# Sheet1.net
KiCad netlist of a schematic drawn in Altium Designer
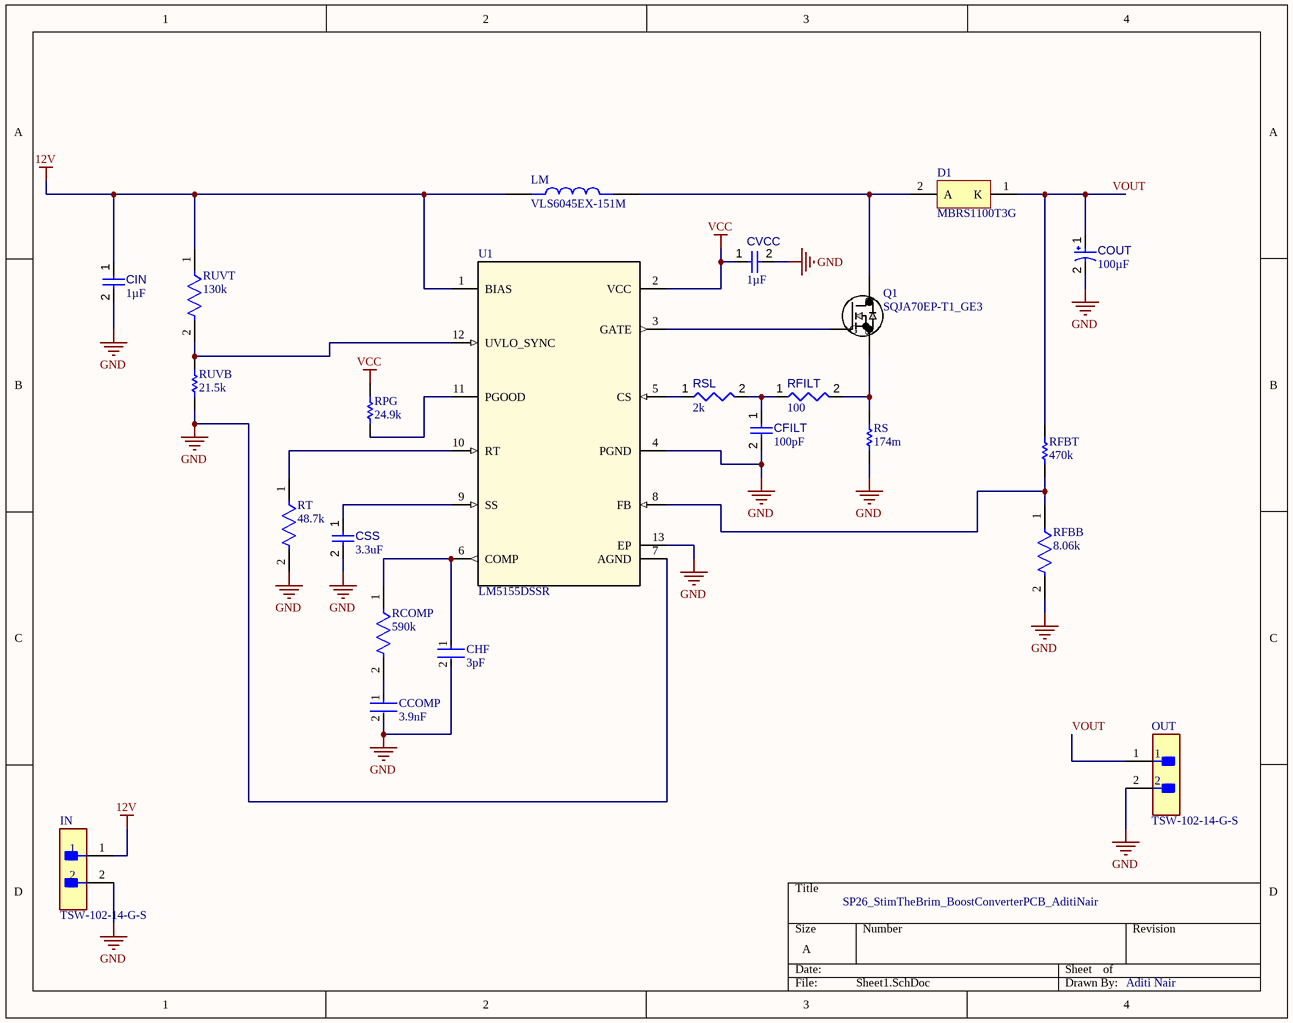
[diagram p0: Sheet1.SchDoc]

(export (version "E")
  (design (tool "Eeschema 10.0.6"))
  (components
    (comp (ref "CCOMP")
      (value "3.9nF")
      (footprint "FP-C1206C-EB-MFG")
      (description "C1206 3,900 pF C0G 5.00% 250 V")
      (fields
        (field (name "MANUFACTURER PART NUMBER") "C1206C392JAGACTU")
        (field (name "OCTOPART") "https://octopart.com/c1206c392jagactu-kemet-88376556")
      )
      (libsource (lib "Altium Content Vault") (part "b4654b650e69147ec39a6b967a45e02"))
    )
    (comp (ref "CFILT")
      (value "100pF")
      (footprint "CAPC0603(1608)100_L")
      (description "Chip Capacitor, 4.7µF +/-20%, 10V, 0603, Thickness 1 mm")
      (fields (field (name "TOLERANCE") "10%"))
      (libsource (lib "Aditi Nair") (part "CAP-NP-2"))
    )
    (comp (ref "CHF")
      (value "3pF")
      (footprint "FP-C0603C-CF-MFG")
      (description "CAP CER 3PF 50V NP0 0603")
      (fields
        (field (name "MANUFACTURER PART NUMBER") "C0603C309D5GAC7867")
        (field (name "MANUFACTURER") "KEMET")
      )
      (libsource (lib "Altium Content Vault") (part "b4654b650e69147ec39a6b967a45e02"))
    )
    (comp (ref "CIN")
      (value "1µF")
      (footprint "CAPC1608X90X35ML15T15")
      (description "Chip Capacitor, 1 uF, +/- 10%, 16 V, 0603 (1608 Metric)")
      (fields (field (name "TOLERANCE") "10%") (field (name "Comment") "Capacitor 1uF +/- 10% 16V 0603"))
      (libsource (lib "Aditi Nair") (part "CAP-NP-2"))
    )
    (comp (ref "COUT")
      (value "100µF")
      (footprint "CAPPR65-500-1600X1000X1700")
      (description "Aluminum Electrolytic Capacitor, 100 uF, +/- 20%, 100 V, -40 to 85 degC, 2-Pin THD, RoHS, Bulk")
      (fields (field (name "MANUFACTURER") "Panasonic") (field (name "TOLERANCE") "20%"))
      (libsource (lib "Aditi Nair") (part "CAP-P-2"))
    )
    (comp (ref "CSS")
      (value "3.3uF")
      (footprint "CAPC1608X90X35ML15T15")
      (description "Chip Capacitor, 1 uF, +/- 10%, 16 V, 0603 (1608 Metric)")
      (fields (field (name "TOLERANCE") "10%") (field (name "Comment") "Capacitor 1uF +/- 10% 16V 0603"))
      (libsource (lib "Aditi Nair") (part "CAP-NP-2"))
    )
    (comp (ref "CVCC")
      (value "1µF")
      (footprint "CAPC1608X90X35ML15T15")
      (description "Chip Capacitor, 1 uF, +/- 10%, 16 V, 0603 (1608 Metric)")
      (fields (field (name "TOLERANCE") "10%") (field (name "Comment") "Capacitor 1uF +/- 10% 16V 0603"))
      (libsource (lib "Aditi Nair") (part "CAP-NP-2"))
    )
    (comp (ref "D1")
      (value "MBRS1100T3G")
      (footprint "ONSC-SMB-2-403A-03_H_V")
      (description "Schottky Power Rectifier, Surface Mount Power Package, 2-Pin SMB, Pb-Free, Tape and Reel")
      (fields (field (name "MANUFACTURER") "On Semiconductor"))
      (libsource (lib "Altium Content Vault") (part "ONSC-D-K1A2-2_A"))
    )
    (comp (ref "IN")
      (value "TSW-102-14-G-S")
      (footprint "FP-TSW-102-14-G-S-MFG")
      (description "CONN HEADER VERT 2POS 2.54MM")
      (libsource (lib "") (part "88c1139f9d239099ffebecbe3f7647a_1"))
    )
    (comp (ref "LM")
      (value "VLS6045EX-151M")
      (footprint "IND_VLS6045EX-151M")
      (description "Inductor Power Shielded Wirewound 150uH 20% 100KHz Ferrite 700mA 760mOhm DCR 2424 T/R")
      (fields (field (name "MF") "TDK"))
      (libsource (lib "VLS6045EX-151M") (part "VLS6045EX-151M"))
    )
    (comp (ref "OUT")
      (value "TSW-102-14-G-S")
      (footprint "FP-TSW-102-14-G-S-MFG")
      (description "CONN HEADER VERT 2POS 2.54MM")
      (libsource (lib "Altium Content Vault") (part "88c1139f9d239099ffebecbe3f7647a"))
    )
    (comp (ref "Q1")
      (value "SQJA70EP-T1_GE3")
      (footprint "SOT_6EP-T1_GE3_VIS")
      (description "N-CHANNEL 100-V (D-S) 175C MOSFET")
      (fields (field (name "COPYRIGHT") "Copyright (C) 2026 Ultra Librarian. All rights reserved."))
      (libsource (lib "SQJA70EP-T1_GE3") (part "SQJA70EP-T1_GE3"))
    )
    (comp (ref "RCOMP")
      (value "590k")
      (footprint "FP-TFCR0805-MFG")
      (description "RES Thin Film,  8.45kΩ, 0.5%, 0.1W, 25ppm/°C, 0805")
      (libsource (lib "Altium Content Vault") (part "1029c3af85768c4190bb7ad29bc67b5"))
    )
    (comp (ref "RFBB")
      (value "8.06k")
      (footprint "FP-RK73H1J-MFG")
      (description "8.06kΩ ±0.5% 0.1W Chip Resistor 0603 Thick Film AEC-Q200 Qualified")
      (fields (field (name "TOLERANCE") "0.5%"))
      (libsource (lib "Altium Content Vault") (part "1029c3af85768c4190bb7ad29bc67b5"))
    )
    (comp (ref "RFBT")
      (value "470k")
      (footprint "RESC0603(1608)_N")
      (description "470K 0.1W 5% 0603 (1608 Metric)  SMD")
      (fields (field (name "TOLERANCE") "5 %") (field (name "POWER") "0.1 W"))
      (libsource (lib "Altium Content Vault") (part "RES"))
    )
    (comp (ref "RFILT")
      (value "100")
      (footprint "RESC0402(1005)_L")
      (description "Chip Resistor, 100 Ohms, +/-1 %, 63 mW, -55 to 155 degC, 0402")
      (fields (field (name "POWER") "63mW") (field (name "TOLERANCE") "1%"))
      (libsource (lib "Aditi Nair") (part "RES-2"))
    )
    (comp (ref "RPG")
      (value "24.9k")
      (footprint "RESC1005X40X25NL05T10")
      (fields (field (name "PART NUMBER") "RC0402FR-07249KL") (field (name "MANUFACTURER") "Yageo / Phycomp"))
      (libsource (lib "Altium Content Vault") (part "RES"))
    )
    (comp (ref "RS")
      (value "174m")
      (footprint "RESC3116X65X40LL10T20")
      (fields (field (name "PART NUMBER") "RC1206FR-10750RL") (field (name "MANUFACTURER") "Yageo"))
      (libsource (lib "Altium Content Vault") (part "RES"))
    )
    (comp (ref "RSL")
      (value "2k")
      (footprint "RESC0402(1005)_L")
      (description "Chip Resistor, 2 kOhms, +/-5 %, 63 mW, -55 to 155 degC, 0402")
      (fields (field (name "TOLERANCE") "5%") (field (name "POWER") "63mW"))
      (libsource (lib "Aditi Nair") (part "RES-2"))
    )
    (comp (ref "RT")
      (value "48.7k")
      (footprint "FP-RN73R1E-IPC_B")
      (description "48.7kΩ ±1% 0.063W, 1/16W Chip Resistor 0402 (1005 Metric) Moisture Resistant Thin Film")
      (libsource (lib "Altium Content Vault") (part "1029c3af85768c4190bb7ad29bc67b5"))
    )
    (comp (ref "RUVB")
      (value "21.5k")
      (footprint "RESC0402(1005)_M")
      (description "21K5 0.063W 1% 0402 (1005 Metric)  SMD")
      (fields (field (name "TOLERANCE") "1 %") (field (name "POWER") "0.063 W"))
      (libsource (lib "Altium Content Vault") (part "RES"))
    )
    (comp (ref "RUVT")
      (value "130k")
      (footprint "FP-RMCF1206-MFG")
      (description "130kΩ ±5% 0.25W 1206 Thick Film Chip Resistor AEC-Q200 compliant")
      (fields (field (name "TOLERANCE") "5%"))
      (libsource (lib "Altium Content Vault") (part "1029c3af85768c4190bb7ad29bc67b5"))
    )
    (comp (ref "U1")
      (value "LM5155DSSR")
      (footprint "DSS0012B")
      (description "2.2-MHz wide VIN, 1.5-A MOSFET driver, non-synchronous boost controller 12-WSON -40 to 125")
      (fields (field (name "COPYRIGHT") "Copyright (C) 2025 Ultra Librarian. All rights reserved."))
      (libsource (lib "LM5155DSSR") (part "LM5155DSSR"))
    )
  )
  (nets
    (net (code "1") (name "/VOUT") (class "Default")
      (node (ref "COUT") (pin "1") (pinfunction "1_1") (pintype "passive"))
      (node (ref "D1") (pin "1") (pinfunction "K_1") (pintype "passive"))
      (node (ref "OUT") (pin "1") (pinfunction "1_1") (pintype "passive"))
      (node (ref "RFBT") (pin "1") (pinfunction "1_1") (pintype "passive"))
    )
    (net (code "2") (name "12V") (class "Default")
      (node (ref "CIN") (pin "1") (pinfunction "1_1") (pintype "passive"))
      (node (ref "IN") (pin "1") (pinfunction "1_1") (pintype "passive"))
      (node (ref "LM") (pin "1") (pinfunction "1_1") (pintype "passive"))
      (node (ref "RUVT") (pin "1") (pinfunction "1_1") (pintype "passive"))
      (node (ref "U1") (pin "1") (pinfunction "BIAS_1") (pintype "power_in"))
    )
    (net (code "3") (name "GND") (class "Default")
      (node (ref "CCOMP") (pin "2") (pinfunction "2_2") (pintype "passive"))
      (node (ref "CFILT") (pin "2") (pinfunction "2_2") (pintype "passive"))
      (node (ref "CHF") (pin "2") (pinfunction "2_2") (pintype "passive"))
      (node (ref "CIN") (pin "2") (pinfunction "2_2") (pintype "passive"))
      (node (ref "COUT") (pin "2") (pinfunction "2_2") (pintype "passive"))
      (node (ref "CSS") (pin "2") (pinfunction "2_2") (pintype "passive"))
      (node (ref "CVCC") (pin "2") (pinfunction "2_2") (pintype "passive"))
      (node (ref "IN") (pin "2") (pinfunction "2_2") (pintype "passive"))
      (node (ref "OUT") (pin "2") (pinfunction "2_2") (pintype "passive"))
      (node (ref "RFBB") (pin "2") (pinfunction "2_2") (pintype "passive"))
      (node (ref "RS") (pin "1") (pinfunction "1_1") (pintype "passive"))
      (node (ref "RT") (pin "2") (pinfunction "2_2") (pintype "passive"))
      (node (ref "RUVB") (pin "2") (pinfunction "2_2") (pintype "passive"))
      (node (ref "U1") (pin "13") (pinfunction "EP_13") (pintype "passive"))
      (node (ref "U1") (pin "4") (pinfunction "PGND_4") (pintype "power_in"))
      (node (ref "U1") (pin "7") (pinfunction "AGND_7") (pintype "power_in"))
    )
    (net (code "4") (name "Net-(CCOMP-Pad1)") (class "Default")
      (node (ref "CCOMP") (pin "1") (pinfunction "1_1") (pintype "passive"))
      (node (ref "RCOMP") (pin "2") (pinfunction "2_2") (pintype "passive"))
    )
    (net (code "5") (name "Net-(CFILT-Pad1)") (class "Default")
      (node (ref "CFILT") (pin "1") (pinfunction "1_1") (pintype "passive"))
      (node (ref "RFILT") (pin "1") (pinfunction "1_1") (pintype "passive"))
      (node (ref "RSL") (pin "2") (pinfunction "2_2") (pintype "passive"))
    )
    (net (code "6") (name "Net-(D1-A)") (class "Default")
      (node (ref "D1") (pin "2") (pinfunction "A_2") (pintype "passive"))
      (node (ref "LM") (pin "2") (pinfunction "2_2") (pintype "passive"))
      (node (ref "Q1") (pin "5") (pinfunction "D_5") (pintype "passive"))
    )
    (net (code "7") (name "Net-(Q1-G)") (class "Default")
      (node (ref "Q1") (pin "4") (pinfunction "G_4") (pintype "passive"))
      (node (ref "U1") (pin "3") (pinfunction "GATE_3") (pintype "output"))
    )
    (net (code "8") (name "Net-(Q1-S)") (class "Default")
      (node (ref "Q1") (pin "2") (pinfunction "S_2") (pintype "passive"))
      (node (ref "RFILT") (pin "2") (pinfunction "2_2") (pintype "passive"))
      (node (ref "RS") (pin "2") (pinfunction "2_2") (pintype "passive"))
    )
    (net (code "9") (name "Net-(U1-COMP)") (class "Default")
      (node (ref "CHF") (pin "1") (pinfunction "1_1") (pintype "passive"))
      (node (ref "RCOMP") (pin "1") (pinfunction "1_1") (pintype "passive"))
      (node (ref "U1") (pin "6") (pinfunction "COMP_6") (pintype "output"))
    )
    (net (code "10") (name "Net-(U1-CS)") (class "Default")
      (node (ref "RSL") (pin "1") (pinfunction "1_1") (pintype "passive"))
      (node (ref "U1") (pin "5") (pinfunction "CS_5") (pintype "input"))
    )
    (net (code "11") (name "Net-(U1-FB)") (class "Default")
      (node (ref "RFBB") (pin "1") (pinfunction "1_1") (pintype "passive"))
      (node (ref "RFBT") (pin "2") (pinfunction "2_2") (pintype "passive"))
      (node (ref "U1") (pin "8") (pinfunction "FB_8") (pintype "input"))
    )
    (net (code "12") (name "Net-(U1-PGOOD)") (class "Default")
      (node (ref "RPG") (pin "1") (pinfunction "1_1") (pintype "passive"))
      (node (ref "U1") (pin "11") (pinfunction "PGOOD_11") (pintype "open_collector"))
    )
    (net (code "13") (name "Net-(U1-RT)") (class "Default")
      (node (ref "RT") (pin "1") (pinfunction "1_1") (pintype "passive"))
      (node (ref "U1") (pin "10") (pinfunction "RT_10") (pintype "input"))
    )
    (net (code "14") (name "Net-(U1-SS)") (class "Default")
      (node (ref "CSS") (pin "1") (pinfunction "1_1") (pintype "passive"))
      (node (ref "U1") (pin "9") (pinfunction "SS_9") (pintype "input"))
    )
    (net (code "15") (name "Net-(U1-UVLO_SYNC)") (class "Default")
      (node (ref "RUVB") (pin "1") (pinfunction "1_1") (pintype "passive"))
      (node (ref "RUVT") (pin "2") (pinfunction "2_2") (pintype "passive"))
      (node (ref "U1") (pin "12") (pinfunction "UVLO_SYNC_12") (pintype "input"))
    )
    (net (code "16") (name "VCC") (class "Default")
      (node (ref "CVCC") (pin "1") (pinfunction "1_1") (pintype "passive"))
      (node (ref "RPG") (pin "2") (pinfunction "2_2") (pintype "passive"))
      (node (ref "U1") (pin "2") (pinfunction "VCC_2") (pintype "power_in"))
    )
  )
)
